# Power.net
KiCad netlist of a schematic drawn in Altium Designer
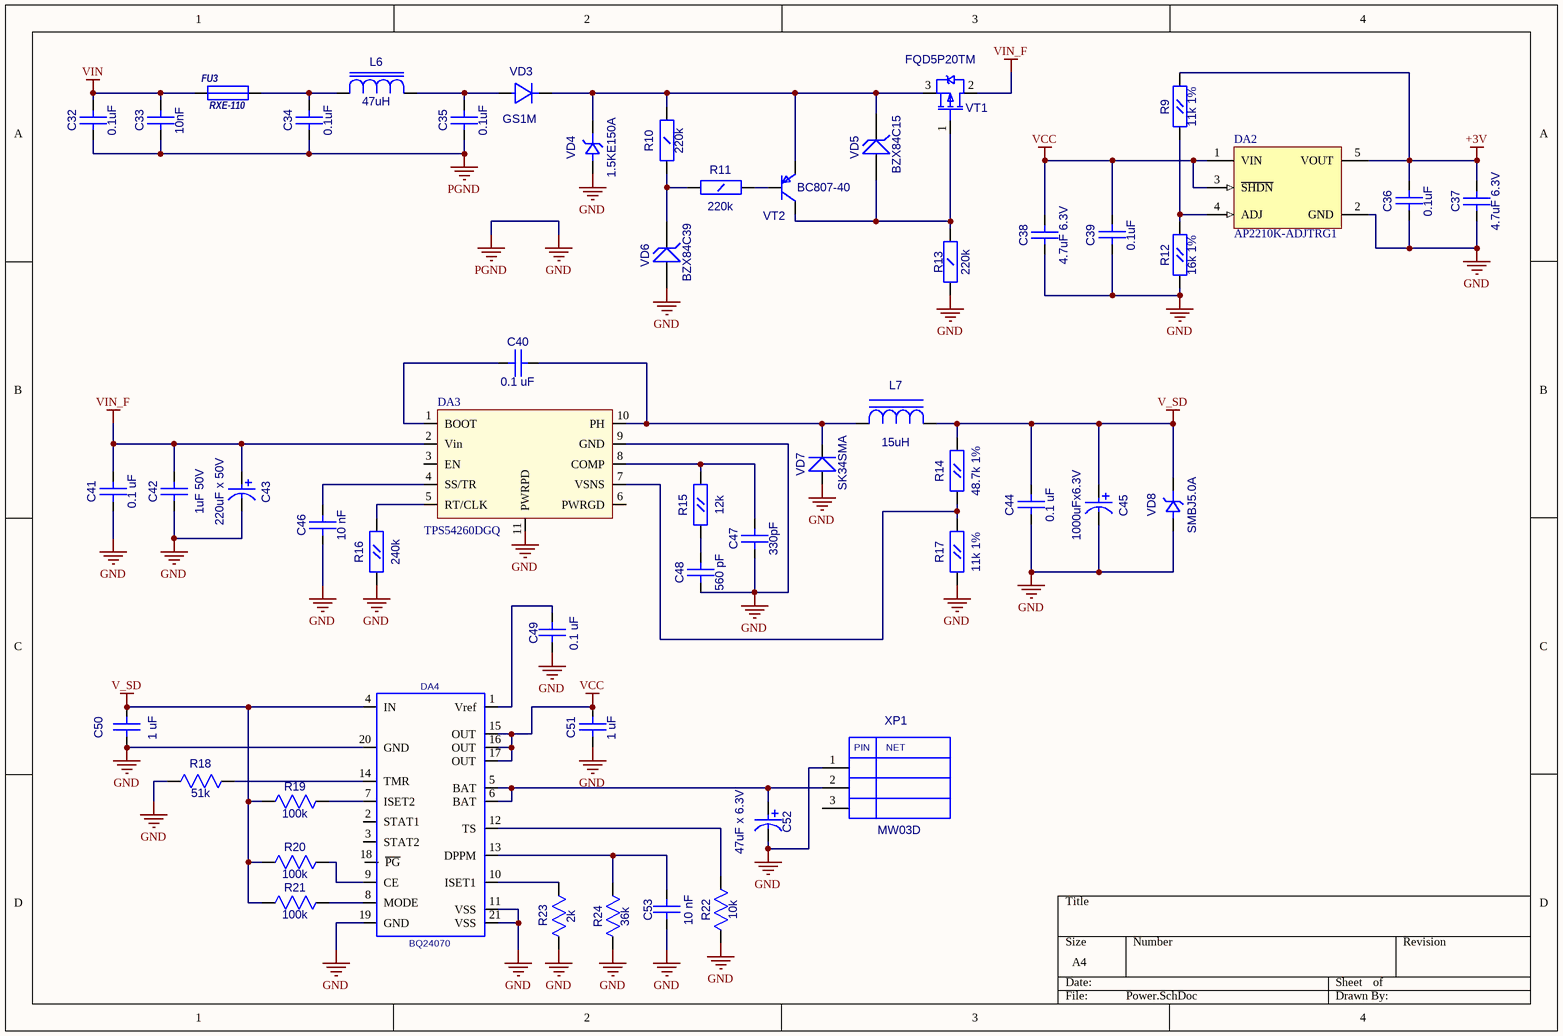
[diagram p0: Power.SchDoc]

(export (version "E")
  (design (tool "Eeschema 10.0.6"))
  (components
    (comp (ref "C32")
      (value "0.1uF")
      (footprint "CC1206")
      (description "CC1206")
      (libsource (lib "gprs_modem_2") (part "CC1206"))
    )
    (comp (ref "C33")
      (value "10nF")
      (footprint "CC1206")
      (description "CC1206")
      (libsource (lib "gprs_modem_2") (part "CC1206"))
    )
    (comp (ref "C34")
      (value "0.1uF")
      (footprint "CC1206")
      (description "CC1206")
      (libsource (lib "gprs_modem_2") (part "CC1206"))
    )
    (comp (ref "C35")
      (value "0.1uF")
      (footprint "CC1206")
      (description "CC1206")
      (libsource (lib "gprs_modem_2") (part "CC1206"))
    )
    (comp (ref "C36")
      (value "0.1uF")
      (footprint "CC0603")
      (description "CC0603")
      (libsource (lib "gprs_modem_2") (part "CC0603"))
    )
    (comp (ref "C37")
      (value "4.7uF 6.3V")
      (footprint "CC0805")
      (description "CC0805")
      (libsource (lib "gprs_modem_2") (part "CC0805"))
    )
    (comp (ref "C38")
      (value "4.7uF 6.3V")
      (footprint "CC0805")
      (description "CC0805")
      (libsource (lib "gprs_modem_2") (part "CC0805"))
    )
    (comp (ref "C39")
      (value "0.1uF")
      (footprint "CC0603")
      (description "CC0603")
      (libsource (lib "gprs_modem_2") (part "CC0603"))
    )
    (comp (ref "C40")
      (value "0.1 uF")
      (footprint "CC0603")
      (description "CC0603")
      (libsource (lib "gprs_modem_2") (part "CC0603"))
    )
    (comp (ref "C41")
      (value "0.1 uF")
      (footprint "CC0603")
      (description "CC0603")
      (libsource (lib "gprs_modem_2") (part "CC0603"))
    )
    (comp (ref "C42")
      (value "1uF 50V")
      (footprint "CC1206")
      (description "CC1206")
      (libsource (lib "gprs_modem_2") (part "CC1206"))
    )
    (comp (ref "C43")
      (value "220uF x 50V")
      (footprint "CC16X10_CAP0.5(1)(Primary)")
      (description "CAP0.5(1)")
      (libsource (lib "gprs_modem") (part "CAP0.5(1)"))
    )
    (comp (ref "C44")
      (value "0.1 uF")
      (footprint "CC0603")
      (description "CC0603")
      (libsource (lib "*") (part "CC0603"))
    )
    (comp (ref "C45")
      (value "1000uFx6.3V")
      (footprint "CC8X3.5")
      (description "CAP0.35")
      (libsource (lib "gprs_modem_2") (part "CAP0.35"))
    )
    (comp (ref "C46")
      (value "10 nF")
      (footprint "CC0603")
      (description "CC0603")
      (libsource (lib "gprs_modem_2") (part "CC0603"))
    )
    (comp (ref "C47")
      (value "330pF")
      (footprint "CC0603")
      (description "CC0603")
      (libsource (lib "gprs_modem_2") (part "CC0603"))
    )
    (comp (ref "C48")
      (value "560 pF")
      (footprint "CC0603")
      (description "CC0603")
      (libsource (lib "gprs_modem_2") (part "CC0603"))
    )
    (comp (ref "C49")
      (value "0.1 uF")
      (footprint "CC0603-3M")
      (description "CC0603")
      (libsource (lib "gprs_modem") (part "CC0603"))
    )
    (comp (ref "C50")
      (value "1 uF")
      (footprint "CC0603-3M")
      (description "CC0603")
      (libsource (lib "*") (part "CC0603"))
    )
    (comp (ref "C51")
      (value "1 uF")
      (footprint "CC0603-3M")
      (description "CC0603")
      (libsource (lib "*") (part "CC0603"))
    )
    (comp (ref "C52")
      (value "47uF x 6.3V")
      (footprint "TAJ-B-1M")
      (description "TAJ-B")
      (libsource (lib "*") (part "TAJ-B"))
    )
    (comp (ref "C53")
      (value "10 nF")
      (footprint "CC0603-3M")
      (description "CC0603")
      (libsource (lib "gprs_modem") (part "CC0603"))
    )
    (comp (ref "DA2")
      (value "AP2210K-ADJTRG1")
      (footprint "SOT23-5")
      (fields (field (name "PUBLISHER") "Altium Limited"))
      (libsource (lib "gprs_modem_2") (part "MCP1824T-ADJE/OT"))
    )
    (comp (ref "DA3")
      (value "TPS54260DGQ")
      (footprint "S-PDSO-G10")
      (libsource (lib "gprs_modem") (part "TPS54260DGQ"))
    )
    (comp (ref "DA4")
      (value "BQ24070")
      (footprint "P-PQFP-N20")
      (libsource (lib "gprs_modem") (part "BQ24070"))
    )
    (comp (ref "FU3") (value "RXE-110") (footprint "RXE-110") (libsource (lib "gprs_modem") (part "RXE-110")))
    (comp (ref "L6")
      (value "47uH")
      (footprint "SDR0603")
      (description "SDR0603")
      (libsource (lib "gprs_modem_2") (part "SDR0603"))
    )
    (comp (ref "L7")
      (value "15uH")
      (footprint "SDR0805")
      (description "SDR0805")
      (libsource (lib "gprs_modem") (part "SDR0805"))
    )
    (comp (ref "R9")
      (value "11k 1%")
      (footprint "RC0603")
      (description "RC0603")
      (libsource (lib "gprs_modem_2") (part "RC0603"))
    )
    (comp (ref "R10")
      (value "220k")
      (footprint "RC1206")
      (description "RC1206")
      (libsource (lib "gprs_modem_2") (part "RC1206"))
    )
    (comp (ref "R11")
      (value "220k")
      (footprint "RC1206")
      (description "RC1206")
      (libsource (lib "gprs_modem_2") (part "RC1206"))
    )
    (comp (ref "R12")
      (value "16k 1%")
      (footprint "RC0603")
      (description "RC0603")
      (libsource (lib "gprs_modem_2") (part "RC0603"))
    )
    (comp (ref "R13")
      (value "220k")
      (footprint "RC1206")
      (description "RC1206")
      (libsource (lib "gprs_modem_2") (part "RC1206"))
    )
    (comp (ref "R14")
      (value "48.7k 1%")
      (footprint "RC0603")
      (description "RC0603")
      (libsource (lib "gprs_modem_2") (part "RC0603"))
    )
    (comp (ref "R15")
      (value "12k")
      (footprint "RC0603")
      (description "RC0603")
      (libsource (lib "gprs_modem_2") (part "RC0603"))
    )
    (comp (ref "R16")
      (value "240k")
      (footprint "RC0603")
      (description "RC0603")
      (libsource (lib "gprs_modem_2") (part "RC0603"))
    )
    (comp (ref "R17")
      (value "11k 1%")
      (footprint "RC0603")
      (description "RC0603")
      (libsource (lib "gprs_modem_2") (part "RC0603"))
    )
    (comp (ref "R18")
      (value "51k")
      (footprint "RC0603-3M")
      (description "RC0603")
      (libsource (lib "*") (part "RC0603"))
    )
    (comp (ref "R19")
      (value "100k")
      (footprint "RC0603-3M")
      (description "RC0603")
      (libsource (lib "*") (part "RC0603"))
    )
    (comp (ref "R20")
      (value "100k")
      (footprint "RC0603-3M")
      (description "RC0603")
      (libsource (lib "*") (part "RC0603"))
    )
    (comp (ref "R21")
      (value "100k")
      (footprint "RC0603-3M")
      (description "RC0603")
      (libsource (lib "*") (part "RC0603"))
    )
    (comp (ref "R22")
      (value "10k")
      (footprint "RC0603-3M")
      (description "RC0603")
      (libsource (lib "*") (part "RC0603"))
    )
    (comp (ref "R23")
      (value "2k")
      (footprint "RC0603-3M")
      (description "RC0603")
      (libsource (lib "*") (part "RC0603"))
    )
    (comp (ref "R24")
      (value "36k")
      (footprint "RC0603-3M")
      (description "RC0603")
      (libsource (lib "*") (part "RC0603"))
    )
    (comp (ref "VD3") (value "GS1M") (footprint "SMA") (libsource (lib "gprs_modem") (part "GS1M")))
    (comp (ref "VD4")
      (value "1.5KE150A")
      (footprint "DO-201")
      (description "1.5KE")
      (libsource (lib "gprs_modem") (part "1.5KE"))
    )
    (comp (ref "VD5")
      (value "BZX84C15")
      (footprint "SOT-23(123)")
      (description "Zener Voltage Regulator Diode")
      (libsource (lib "gprs_modem_2") (part "BZX84"))
    )
    (comp (ref "VD6")
      (value "BZX84C39")
      (footprint "SOT-23(123)")
      (description "Zener Voltage Regulator Diode")
      (libsource (lib "gprs_modem_2") (part "BZX84"))
    )
    (comp (ref "VD7")
      (value "SK34SMA")
      (footprint "SMA")
      (description "Schottky Rectifier")
      (libsource (lib "gprs_modem") (part "SK34SMA"))
    )
    (comp (ref "VD8")
      (value "SMBJ5.0A")
      (footprint "SMB")
      (description "SMBJ")
      (libsource (lib "gprs_modem") (part "SMBJ"))
    )
    (comp (ref "VT1")
      (value "FQD5P20TM")
      (footprint "D-PAK(TO-252AA)")
      (description "HEXFET Power MOSFET")
      (libsource (lib "gprs_modem_2") (part "IRFR9220"))
    )
    (comp (ref "VT2")
      (value "BC807-40")
      (footprint "SOT-23(123)")
      (description "BC857B")
      (libsource (lib "gprs_modem") (part "BC857B"))
    )
    (comp (ref "XP1") (value "MW03D") (footprint "MW03D") (libsource (lib "gprs_modem") (part "MW03D")))
  )
  (nets
    (net (code "1") (name "+3V") (class "Default")
      (node (ref "C36") (pin "1") (pinfunction "A_1") (pintype "passive"))
      (node (ref "C37") (pin "2") (pinfunction "B_2") (pintype "passive"))
      (node (ref "DA2") (pin "5") (pinfunction "VOUT_5") (pintype "power_in"))
      (node (ref "R9") (pin "2") (pinfunction "B_2") (pintype "passive"))
    )
    (net (code "2") (name "GND") (class "Default")
      (node (ref "C32") (pin "1") (pinfunction "A_1") (pintype "passive"))
      (node (ref "C33") (pin "1") (pinfunction "A_1") (pintype "passive"))
      (node (ref "C34") (pin "1") (pinfunction "A_1") (pintype "passive"))
      (node (ref "C35") (pin "1") (pinfunction "A_1") (pintype "passive"))
      (node (ref "C36") (pin "2") (pinfunction "B_2") (pintype "passive"))
      (node (ref "C37") (pin "1") (pinfunction "A_1") (pintype "passive"))
      (node (ref "C38") (pin "1") (pinfunction "A_1") (pintype "passive"))
      (node (ref "C39") (pin "2") (pinfunction "B_2") (pintype "passive"))
      (node (ref "C41") (pin "1") (pinfunction "A_1") (pintype "passive"))
      (node (ref "C42") (pin "1") (pinfunction "A_1") (pintype "passive"))
      (node (ref "C43") (pin "1") (pintype "passive"))
      (node (ref "C44") (pin "2") (pinfunction "B_2") (pintype "passive"))
      (node (ref "C45") (pin "2") (pintype "passive"))
      (node (ref "C46") (pin "1") (pinfunction "A_1") (pintype "passive"))
      (node (ref "C47") (pin "1") (pinfunction "A_1") (pintype "passive"))
      (node (ref "C48") (pin "1") (pinfunction "A_1") (pintype "passive"))
      (node (ref "C49") (pin "2") (pinfunction "B_2") (pintype "passive"))
      (node (ref "C50") (pin "2") (pinfunction "B_2") (pintype "passive"))
      (node (ref "C51") (pin "2") (pinfunction "B_2") (pintype "passive"))
      (node (ref "C52") (pin "2") (pinfunction "B_2") (pintype "passive"))
      (node (ref "C53") (pin "2") (pinfunction "B_2") (pintype "passive"))
      (node (ref "DA2") (pin "2") (pinfunction "GND_2") (pintype "power_in"))
      (node (ref "DA3") (pin "11") (pinfunction "PWRPD_11") (pintype "passive"))
      (node (ref "DA3") (pin "9") (pinfunction "GND_9") (pintype "passive"))
      (node (ref "DA4") (pin "11") (pinfunction "VSS_11") (pintype "passive"))
      (node (ref "DA4") (pin "19") (pinfunction "GND_19") (pintype "passive"))
      (node (ref "DA4") (pin "20") (pinfunction "GND_20") (pintype "passive"))
      (node (ref "DA4") (pin "21") (pinfunction "VSS_21") (pintype "passive"))
      (node (ref "R12") (pin "1") (pinfunction "A_1") (pintype "passive"))
      (node (ref "R13") (pin "2") (pinfunction "B_2") (pintype "passive"))
      (node (ref "R16") (pin "1") (pinfunction "A_1") (pintype "passive"))
      (node (ref "R17") (pin "1") (pinfunction "A_1") (pintype "passive"))
      (node (ref "R18") (pin "1") (pinfunction "A_1") (pintype "passive"))
      (node (ref "R22") (pin "1") (pinfunction "A_1") (pintype "passive"))
      (node (ref "R23") (pin "1") (pinfunction "A_1") (pintype "passive"))
      (node (ref "R24") (pin "1") (pinfunction "A_1") (pintype "passive"))
      (node (ref "VD4") (pin "1") (pinfunction "A_1") (pintype "passive"))
      (node (ref "VD6") (pin "1") (pinfunction "A_1") (pintype "passive"))
      (node (ref "VD7") (pin "1") (pinfunction "A_1") (pintype "passive"))
      (node (ref "VD8") (pin "1") (pinfunction "A_1") (pintype "passive"))
      (node (ref "XP1") (pin "1") (pinfunction "1_1") (pintype "passive"))
    )
    (net (code "3") (name "Net-(C34-B)") (class "Default")
      (node (ref "C34") (pin "2") (pinfunction "B_2") (pintype "passive"))
      (node (ref "FU3") (pin "2") (pintype "passive"))
      (node (ref "L6") (pin "1") (pintype "passive"))
    )
    (net (code "4") (name "Net-(C35-B)") (class "Default")
      (node (ref "C35") (pin "2") (pinfunction "B_2") (pintype "passive"))
      (node (ref "L6") (pin "2") (pintype "passive"))
      (node (ref "VD3") (pin "1") (pinfunction "A_1") (pintype "passive"))
    )
    (net (code "5") (name "Net-(C40-A)") (class "Default")
      (node (ref "C40") (pin "1") (pinfunction "A_1") (pintype "passive"))
      (node (ref "DA3") (pin "1") (pinfunction "BOOT_1") (pintype "passive"))
    )
    (net (code "6") (name "Net-(C40-B)") (class "Default")
      (node (ref "C40") (pin "2") (pinfunction "B_2") (pintype "passive"))
      (node (ref "DA3") (pin "10") (pinfunction "PH_10") (pintype "passive"))
      (node (ref "L7") (pin "1") (pinfunction "C_1") (pintype "passive"))
      (node (ref "VD7") (pin "2") (pinfunction "K_2") (pintype "passive"))
    )
    (net (code "7") (name "Net-(C46-B)") (class "Default")
      (node (ref "C46") (pin "2") (pinfunction "B_2") (pintype "passive"))
      (node (ref "DA3") (pin "4") (pinfunction "SS/TR_4") (pintype "passive"))
    )
    (net (code "8") (name "Net-(C47-B)") (class "Default")
      (node (ref "C47") (pin "2") (pinfunction "B_2") (pintype "passive"))
      (node (ref "DA3") (pin "8") (pinfunction "COMP_8") (pintype "passive"))
      (node (ref "R15") (pin "2") (pinfunction "B_2") (pintype "passive"))
    )
    (net (code "9") (name "Net-(C48-B)") (class "Default")
      (node (ref "C48") (pin "2") (pinfunction "B_2") (pintype "passive"))
      (node (ref "R15") (pin "1") (pinfunction "A_1") (pintype "passive"))
    )
    (net (code "10") (name "Net-(C49-A)") (class "Default")
      (node (ref "C49") (pin "1") (pinfunction "A_1") (pintype "passive"))
      (node (ref "DA4") (pin "1") (pinfunction "Vref_1") (pintype "passive"))
    )
    (net (code "11") (name "Net-(C52-A)") (class "Default")
      (node (ref "C52") (pin "1") (pinfunction "A_1") (pintype "passive"))
      (node (ref "DA4") (pin "5") (pinfunction "BAT_5") (pintype "passive"))
      (node (ref "DA4") (pin "6") (pinfunction "BAT_6") (pintype "passive"))
      (node (ref "XP1") (pin "2") (pinfunction "2_2") (pintype "passive"))
    )
    (net (code "12") (name "Net-(C53-A)") (class "Default")
      (node (ref "C53") (pin "1") (pinfunction "A_1") (pintype "passive"))
      (node (ref "DA4") (pin "13") (pinfunction "DPPM_13") (pintype "passive"))
      (node (ref "R24") (pin "2") (pinfunction "B_2") (pintype "passive"))
    )
    (net (code "13") (name "Net-(DA2-ADJ)") (class "Default")
      (node (ref "DA2") (pin "4") (pinfunction "ADJ_4") (pintype "input"))
      (node (ref "R12") (pin "2") (pinfunction "B_2") (pintype "passive"))
      (node (ref "R9") (pin "1") (pinfunction "A_1") (pintype "passive"))
    )
    (net (code "14") (name "Net-(DA3-RT{slash}CLK)") (class "Default")
      (node (ref "DA3") (pin "5") (pinfunction "RT/CLK_5") (pintype "passive"))
      (node (ref "R16") (pin "2") (pinfunction "B_2") (pintype "passive"))
    )
    (net (code "15") (name "Net-(DA3-VSNS)") (class "Default")
      (node (ref "DA3") (pin "7") (pinfunction "VSNS_7") (pintype "passive"))
      (node (ref "R14") (pin "1") (pinfunction "A_1") (pintype "passive"))
      (node (ref "R17") (pin "2") (pinfunction "B_2") (pintype "passive"))
    )
    (net (code "16") (name "Net-(DA4-CE)") (class "Default")
      (node (ref "DA4") (pin "9") (pinfunction "CE_9") (pintype "passive"))
      (node (ref "R20") (pin "2") (pinfunction "B_2") (pintype "passive"))
    )
    (net (code "17") (name "Net-(DA4-ISET1)") (class "Default")
      (node (ref "DA4") (pin "10") (pinfunction "ISET1_10") (pintype "passive"))
      (node (ref "R23") (pin "2") (pinfunction "B_2") (pintype "passive"))
    )
    (net (code "18") (name "Net-(DA4-ISET2)") (class "Default")
      (node (ref "DA4") (pin "7") (pinfunction "ISET2_7") (pintype "passive"))
      (node (ref "R19") (pin "2") (pinfunction "B_2") (pintype "passive"))
    )
    (net (code "19") (name "Net-(DA4-MODE)") (class "Default")
      (node (ref "DA4") (pin "8") (pinfunction "MODE_8") (pintype "passive"))
      (node (ref "R21") (pin "2") (pinfunction "B_2") (pintype "passive"))
    )
    (net (code "20") (name "Net-(DA4-TMR)") (class "Default")
      (node (ref "DA4") (pin "14") (pinfunction "TMR_14") (pintype "passive"))
      (node (ref "R18") (pin "2") (pinfunction "B_2") (pintype "passive"))
    )
    (net (code "21") (name "Net-(DA4-TS)") (class "Default")
      (node (ref "DA4") (pin "12") (pinfunction "TS_12") (pintype "passive"))
      (node (ref "R22") (pin "2") (pinfunction "B_2") (pintype "passive"))
    )
    (net (code "22") (name "Net-(R10-A)") (class "Default")
      (node (ref "R10") (pin "1") (pinfunction "A_1") (pintype "passive"))
      (node (ref "R11") (pin "1") (pinfunction "A_1") (pintype "passive"))
      (node (ref "VD6") (pin "3") (pinfunction "K_3") (pintype "passive"))
    )
    (net (code "23") (name "Net-(R10-B)") (class "Default")
      (node (ref "R10") (pin "2") (pinfunction "B_2") (pintype "passive"))
      (node (ref "VD3") (pin "2") (pinfunction "K_2") (pintype "passive"))
      (node (ref "VD4") (pin "2") (pinfunction "K_2") (pintype "passive"))
      (node (ref "VD5") (pin "3") (pinfunction "K_3") (pintype "passive"))
      (node (ref "VT1") (pin "3") (pinfunction "S_3") (pintype "passive"))
      (node (ref "VT2") (pin "2") (pinfunction "E_2") (pintype "passive"))
    )
    (net (code "24") (name "Net-(R11-B)") (class "Default")
      (node (ref "R11") (pin "2") (pinfunction "B_2") (pintype "passive"))
      (node (ref "VT2") (pin "1") (pinfunction "B_1") (pintype "passive"))
    )
    (net (code "25") (name "Net-(R13-A)") (class "Default")
      (node (ref "R13") (pin "1") (pinfunction "A_1") (pintype "passive"))
      (node (ref "VD5") (pin "1") (pinfunction "A_1") (pintype "passive"))
      (node (ref "VT1") (pin "1") (pinfunction "G_1") (pintype "passive"))
      (node (ref "VT2") (pin "3") (pinfunction "C_3") (pintype "passive"))
    )
    (net (code "26") (name "VCC") (class "Default")
      (node (ref "C38") (pin "2") (pinfunction "B_2") (pintype "passive"))
      (node (ref "C39") (pin "1") (pinfunction "A_1") (pintype "passive"))
      (node (ref "C51") (pin "1") (pinfunction "A_1") (pintype "passive"))
      (node (ref "DA2") (pin "1") (pinfunction "VIN_1") (pintype "power_in"))
      (node (ref "DA2") (pin "3") (pinfunction "~{SHDN}_3") (pintype "input"))
      (node (ref "DA4") (pin "15") (pinfunction "OUT_15") (pintype "passive"))
      (node (ref "DA4") (pin "16") (pinfunction "OUT_16") (pintype "passive"))
      (node (ref "DA4") (pin "17") (pinfunction "OUT_17") (pintype "passive"))
    )
    (net (code "27") (name "VIN") (class "Default")
      (node (ref "C32") (pin "2") (pinfunction "B_2") (pintype "passive"))
      (node (ref "C33") (pin "2") (pinfunction "B_2") (pintype "passive"))
      (node (ref "FU3") (pin "1") (pintype "passive"))
    )
    (net (code "28") (name "VIN_F") (class "Default")
      (node (ref "C41") (pin "2") (pinfunction "B_2") (pintype "passive"))
      (node (ref "C42") (pin "2") (pinfunction "B_2") (pintype "passive"))
      (node (ref "C43") (pin "2") (pintype "passive"))
      (node (ref "DA3") (pin "2") (pinfunction "Vin_2") (pintype "passive"))
      (node (ref "VT1") (pin "2") (pinfunction "D_2") (pintype "passive"))
    )
    (net (code "29") (name "V_SD") (class "Default")
      (node (ref "C44") (pin "1") (pinfunction "A_1") (pintype "passive"))
      (node (ref "C45") (pin "1") (pintype "passive"))
      (node (ref "C50") (pin "1") (pinfunction "A_1") (pintype "passive"))
      (node (ref "DA4") (pin "4") (pinfunction "IN_4") (pintype "passive"))
      (node (ref "L7") (pin "2") (pinfunction "A_2") (pintype "passive"))
      (node (ref "R14") (pin "2") (pinfunction "B_2") (pintype "passive"))
      (node (ref "R19") (pin "1") (pinfunction "A_1") (pintype "passive"))
      (node (ref "R20") (pin "1") (pinfunction "A_1") (pintype "passive"))
      (node (ref "R21") (pin "1") (pinfunction "A_1") (pintype "passive"))
      (node (ref "VD8") (pin "2") (pinfunction "K_2") (pintype "passive"))
    )
    (net (code "30") (name "unconnected-(DA3-EN-Pad3)") (class "Default")
      (node (ref "DA3") (pin "3") (pinfunction "EN_3") (pintype "passive"))
    )
    (net (code "31") (name "unconnected-(DA3-PWRGD-Pad6)") (class "Default")
      (node (ref "DA3") (pin "6") (pinfunction "PWRGD_6") (pintype "passive"))
    )
    (net (code "32") (name "unconnected-(DA4-STAT1-Pad2)") (class "Default")
      (node (ref "DA4") (pin "2") (pinfunction "STAT1_2") (pintype "passive"))
    )
    (net (code "33") (name "unconnected-(DA4-STAT2-Pad3)") (class "Default")
      (node (ref "DA4") (pin "3") (pinfunction "STAT2_3") (pintype "passive"))
    )
    (net (code "34") (name "unconnected-(DA4-~{PG}-Pad18)") (class "Default")
      (node (ref "DA4") (pin "18") (pinfunction "~{PG}_18") (pintype "passive"))
    )
    (net (code "35") (name "unconnected-(XP1-Pad3)") (class "Default")
      (node (ref "XP1") (pin "3") (pinfunction "3_3") (pintype "passive"))
    )
  )
)
